# bbr18_ball_led_board.net
KiCad netlist of a schematic drawn in Altium Designer
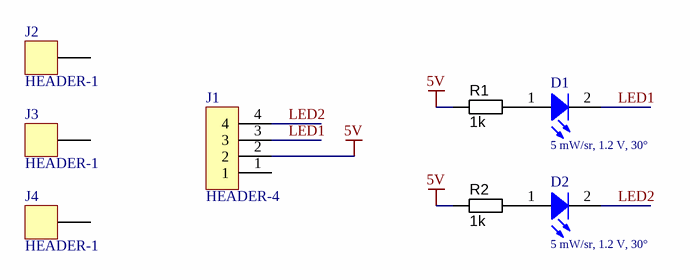
[diagram p0: bbr18_ball_led_board.SchDoc]

(export (version "E")
  (design (tool "Eeschema 10.0.6"))
  (components
    (comp (ref "D1")
      (value "5 mW/sr, 1.2 V, 30°")
      (footprint "WL-SIRW_1206_15412094A3060_reverse use")
      (description "WL-SIRW SMD Infrared Reverse mount Waterclear Dome, size 1206, 5 mW/sr, 1.2 V, 30°")
      (fields (field (name "PART NUMBER") "15412094A3060") (field (name "PUBLISHER") "Wurth Elektronik"))
      (libsource (lib "ALTIUM-WL-SIRW-rev18a") (part "15412094A3060"))
    )
    (comp (ref "D2")
      (value "5 mW/sr, 1.2 V, 30°")
      (footprint "WL-SIRW_1206_15412094A3060_reverse use")
      (description "WL-SIRW SMD Infrared Reverse mount Waterclear Dome, size 1206, 5 mW/sr, 1.2 V, 30°")
      (fields (field (name "PART NUMBER") "15412094A3060") (field (name "PUBLISHER") "Wurth Elektronik"))
      (libsource (lib "ALTIUM-WL-SIRW-rev18a") (part "15412094A3060"))
    )
    (comp (ref "J1")
      (value "HEADER-4")
      (footprint "MICRO-MATCH-MOB-04")
      (libsource (lib "connectors_micromatch") (part "HEADER-4"))
    )
    (comp (ref "J2")
      (value "HEADER-1")
      (footprint "2MM-BANANA-VIA")
      (libsource (lib "connectors") (part "HEADER-1"))
    )
    (comp (ref "J3")
      (value "HEADER-1")
      (footprint "2MM-BANANA-VIA")
      (libsource (lib "connectors") (part "HEADER-1"))
    )
    (comp (ref "J4")
      (value "HEADER-1")
      (footprint "2MM-BANANA-VIA")
      (libsource (lib "connectors") (part "HEADER-1"))
    )
    (comp (ref "R1")
      (value "1k")
      (footprint "RESC1608X55N")
      (description "Resistor SMD chip 1k Ohm 0.1W 5% 0603")
      (fields (field (name "TOLERANCE") "±5%"))
      (libsource (lib "PBL - Resistors") (part "RES_1K_0603_5%"))
    )
    (comp (ref "R2")
      (value "1k")
      (footprint "RESC1608X55N")
      (description "Resistor SMD chip 1k Ohm 0.1W 5% 0603")
      (fields (field (name "TOLERANCE") "±5%"))
      (libsource (lib "PBL - Resistors") (part "RES_1K_0603_5%"))
    )
  )
  (nets
    (net (code "1") (name "/LED1") (class "Default")
      (node (ref "D1") (pin "2") (pinfunction "K_2") (pintype "passive"))
      (node (ref "J1") (pin "3") (pinfunction "3_3") (pintype "passive"))
    )
    (net (code "2") (name "/LED2") (class "Default")
      (node (ref "D2") (pin "2") (pinfunction "K_2") (pintype "passive"))
      (node (ref "J1") (pin "4") (pinfunction "4_4") (pintype "passive"))
    )
    (net (code "3") (name "5V") (class "Default")
      (node (ref "J1") (pin "2") (pinfunction "2_2") (pintype "passive"))
      (node (ref "R1") (pin "1") (pinfunction "1_1") (pintype "passive"))
      (node (ref "R2") (pin "1") (pinfunction "1_1") (pintype "passive"))
    )
    (net (code "4") (name "Net-(D1-A)") (class "Default")
      (node (ref "D1") (pin "1") (pinfunction "A_1") (pintype "passive"))
      (node (ref "R1") (pin "2") (pinfunction "2_2") (pintype "passive"))
    )
    (net (code "5") (name "Net-(D2-A)") (class "Default")
      (node (ref "D2") (pin "1") (pinfunction "A_1") (pintype "passive"))
      (node (ref "R2") (pin "2") (pinfunction "2_2") (pintype "passive"))
    )
    (net (code "6") (name "unconnected-(J1-Pad1)") (class "Default")
      (node (ref "J1") (pin "1") (pinfunction "1_1") (pintype "passive"))
    )
    (net (code "7") (name "unconnected-(J2-Pad1)") (class "Default")
      (node (ref "J2") (pin "1") (pinfunction "1_1") (pintype "passive"))
    )
    (net (code "8") (name "unconnected-(J3-Pad1)") (class "Default")
      (node (ref "J3") (pin "1") (pinfunction "1_1") (pintype "passive"))
    )
    (net (code "9") (name "unconnected-(J4-Pad1)") (class "Default")
      (node (ref "J4") (pin "1") (pinfunction "1_1") (pintype "passive"))
    )
  )
)
